# test2.net
KiCad netlist of a schematic drawn in EAGLE
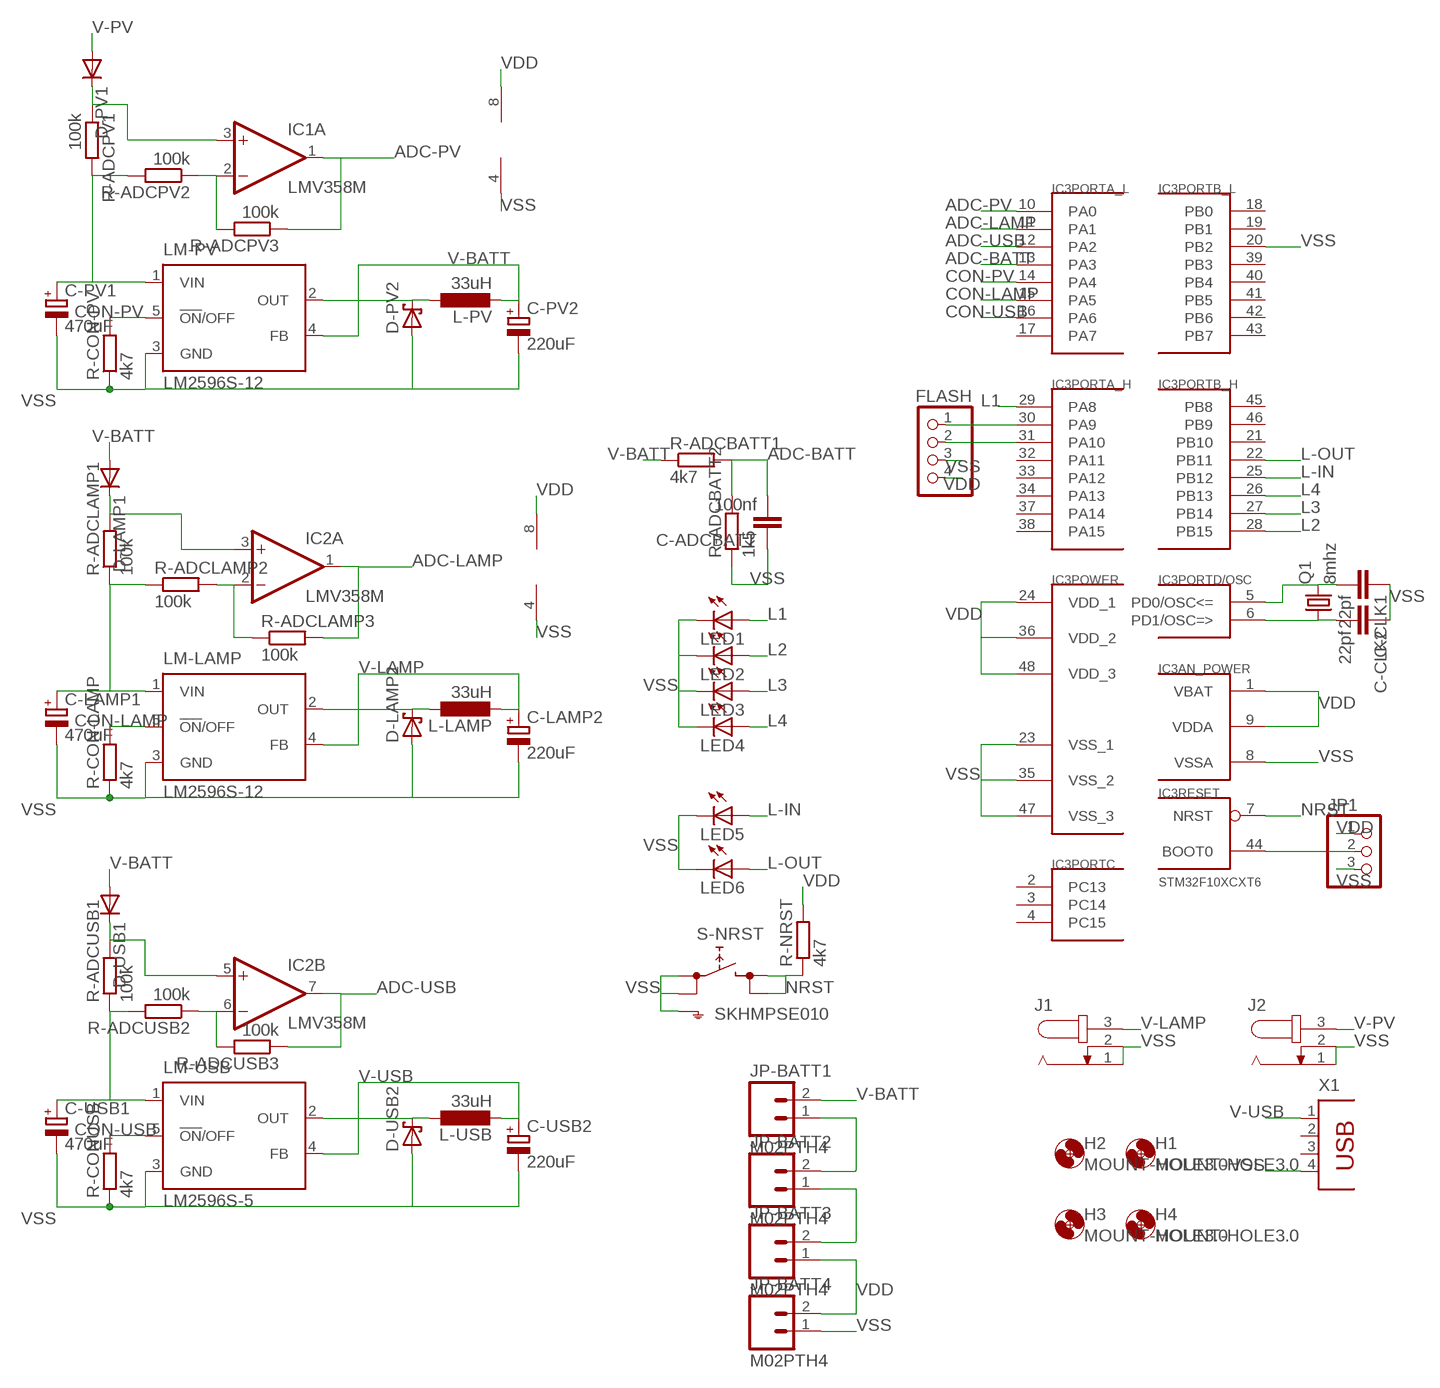
[diagram p0: schematic, sheet 1]

(export (version "E")
  (design (tool "Eeschema 10.0.6"))
  (components
    (comp (ref "C-ADCBATT")
      (value "100nf")
      (footprint "eagle-import:C0805")
      (libsource (lib "eagle-import") (part "C-EUC0805"))
    )
    (comp (ref "C-CLK1")
      (value "22pf")
      (footprint "eagle-import:C0805")
      (libsource (lib "eagle-import") (part "C-EUC0805"))
    )
    (comp (ref "C-CLK2")
      (value "22pf")
      (footprint "eagle-import:C0805")
      (libsource (lib "eagle-import") (part "C-EUC0805"))
    )
    (comp (ref "C-LAMP1")
      (value "470uF")
      (footprint "eagle-import:E2,5-5")
      (libsource (lib "eagle-import") (part "CPOL-EUE2.5-5"))
    )
    (comp (ref "C-LAMP2")
      (value "220uF")
      (footprint "eagle-import:E2,5-5")
      (libsource (lib "eagle-import") (part "CPOL-EUE2.5-5"))
    )
    (comp (ref "C-PV1")
      (value "470uF")
      (footprint "eagle-import:E2,5-5")
      (libsource (lib "eagle-import") (part "CPOL-EUE2.5-5"))
    )
    (comp (ref "C-PV2")
      (value "220uF")
      (footprint "eagle-import:E2,5-5")
      (libsource (lib "eagle-import") (part "CPOL-EUE2.5-5"))
    )
    (comp (ref "C-USB1")
      (value "470uF")
      (footprint "eagle-import:E2,5-5")
      (libsource (lib "eagle-import") (part "CPOL-EUE2.5-5"))
    )
    (comp (ref "C-USB2")
      (value "220uF")
      (footprint "eagle-import:E2,5-5")
      (libsource (lib "eagle-import") (part "CPOL-EUE2.5-5"))
    )
    (comp (ref "D-LAMP1")
      (value "DIODE-DO-214AC")
      (footprint "eagle-import:DO-214AC")
      (libsource (lib "eagle-import") (part "DIODE-DO-214AC"))
    )
    (comp (ref "D-LAMP2")
      (value "SCHOTTKY-DIODE")
      (footprint "eagle-import:DIODE_SMB")
      (libsource (lib "eagle-import") (part "SCHOTTKY-DIODE"))
    )
    (comp (ref "D-PV1")
      (value "DIODE-DO-214AC")
      (footprint "eagle-import:DO-214AC")
      (libsource (lib "eagle-import") (part "DIODE-DO-214AC"))
    )
    (comp (ref "D-PV2")
      (value "SCHOTTKY-DIODE")
      (footprint "eagle-import:DIODE_SMB")
      (libsource (lib "eagle-import") (part "SCHOTTKY-DIODE"))
    )
    (comp (ref "D-USB1")
      (value "DIODE-DO-214AC")
      (footprint "eagle-import:DO-214AC")
      (libsource (lib "eagle-import") (part "DIODE-DO-214AC"))
    )
    (comp (ref "D-USB2")
      (value "SCHOTTKY-DIODE")
      (footprint "eagle-import:DIODE_SMB")
      (libsource (lib "eagle-import") (part "SCHOTTKY-DIODE"))
    )
    (comp (ref "FLASH")
      (value "PINHD-1X4")
      (footprint "eagle-import:1X04")
      (libsource (lib "eagle-import") (part "PINHD-1X4"))
    )
    (comp (ref "H1")
      (value "MOUNT-HOLE3.0")
      (footprint "eagle-import:3,0")
      (libsource (lib "eagle-import") (part "MOUNT-HOLE3.0"))
    )
    (comp (ref "H2")
      (value "MOUNT-HOLE3.0")
      (footprint "eagle-import:3,0")
      (libsource (lib "eagle-import") (part "MOUNT-HOLE3.0"))
    )
    (comp (ref "H3")
      (value "MOUNT-HOLE3.0")
      (footprint "eagle-import:3,0")
      (libsource (lib "eagle-import") (part "MOUNT-HOLE3.0"))
    )
    (comp (ref "H4")
      (value "MOUNT-HOLE3.0")
      (footprint "eagle-import:3,0")
      (libsource (lib "eagle-import") (part "MOUNT-HOLE3.0"))
    )
    (comp (ref "IC1")
      (value "LMV358M")
      (footprint "eagle-import:SO08")
      (libsource (lib "eagle-import") (part "LMV358?M"))
    )
    (comp (ref "IC2")
      (value "LMV358M")
      (footprint "eagle-import:SO08")
      (libsource (lib "eagle-import") (part "LMV358?M"))
    )
    (comp (ref "IC3")
      (value "STM32F10XCXT6")
      (footprint "eagle-import:TQFP48")
      (libsource (lib "eagle-import") (part "STM32F10XCXT6"))
    )
    (comp (ref "J1")
      (value "JACK-PLUG0")
      (footprint "eagle-import:SPC4077")
      (libsource (lib "eagle-import") (part "JACK-PLUG0"))
    )
    (comp (ref "J2")
      (value "JACK-PLUG0")
      (footprint "eagle-import:SPC4077")
      (libsource (lib "eagle-import") (part "JACK-PLUG0"))
    )
    (comp (ref "JP-BATT1")
      (value "M02PTH4")
      (footprint "eagle-import:1X02_XTRA_BIG")
      (libsource (lib "eagle-import") (part "M02PTH4"))
    )
    (comp (ref "JP-BATT2")
      (value "M02PTH4")
      (footprint "eagle-import:1X02_XTRA_BIG")
      (libsource (lib "eagle-import") (part "M02PTH4"))
    )
    (comp (ref "JP-BATT3")
      (value "M02PTH4")
      (footprint "eagle-import:1X02_XTRA_BIG")
      (libsource (lib "eagle-import") (part "M02PTH4"))
    )
    (comp (ref "JP-BATT4")
      (value "M02PTH4")
      (footprint "eagle-import:1X02_XTRA_BIG")
      (libsource (lib "eagle-import") (part "M02PTH4"))
    )
    (comp (ref "JP1")
      (value "PINHD-1X3")
      (footprint "eagle-import:1X03")
      (libsource (lib "eagle-import") (part "PINHD-1X3"))
    )
    (comp (ref "L-LAMP")
      (value "33uH")
      (footprint "eagle-import:POWER-CHOKE_WE-TPC")
      (libsource (lib "eagle-import") (part "L-EUWE-TPC"))
    )
    (comp (ref "L-PV")
      (value "33uH")
      (footprint "eagle-import:POWER-CHOKE_WE-TPC")
      (libsource (lib "eagle-import") (part "L-EUWE-TPC"))
    )
    (comp (ref "L-USB")
      (value "33uH")
      (footprint "eagle-import:POWER-CHOKE_WE-TPC")
      (libsource (lib "eagle-import") (part "L-EUWE-TPC"))
    )
    (comp (ref "LED1")
      (value "LEDCHIP-LED0805")
      (footprint "eagle-import:CHIP-LED0805")
      (libsource (lib "eagle-import") (part "LEDCHIP-LED0805"))
    )
    (comp (ref "LED2")
      (value "LEDCHIP-LED0805")
      (footprint "eagle-import:CHIP-LED0805")
      (libsource (lib "eagle-import") (part "LEDCHIP-LED0805"))
    )
    (comp (ref "LED3")
      (value "LEDCHIP-LED0805")
      (footprint "eagle-import:CHIP-LED0805")
      (libsource (lib "eagle-import") (part "LEDCHIP-LED0805"))
    )
    (comp (ref "LED4")
      (value "LEDCHIP-LED0805")
      (footprint "eagle-import:CHIP-LED0805")
      (libsource (lib "eagle-import") (part "LEDCHIP-LED0805"))
    )
    (comp (ref "LED5")
      (value "LEDCHIP-LED0805")
      (footprint "eagle-import:CHIP-LED0805")
      (libsource (lib "eagle-import") (part "LEDCHIP-LED0805"))
    )
    (comp (ref "LED6")
      (value "LEDCHIP-LED0805")
      (footprint "eagle-import:CHIP-LED0805")
      (libsource (lib "eagle-import") (part "LEDCHIP-LED0805"))
    )
    (comp (ref "LM-LAMP")
      (value "LM2596S-12")
      (footprint "eagle-import:TO263-5")
      (fields (field (name "MF") "NATIONAL SEMICONDUCTOR") (field (name "MPN") "LM2596S-ADJ/NOPB"))
      (libsource (lib "eagle-import") (part "LM2596S"))
    )
    (comp (ref "LM-PV")
      (value "LM2596S-12")
      (footprint "eagle-import:TO263-5")
      (fields (field (name "MF") "NATIONAL SEMICONDUCTOR") (field (name "MPN") "LM2596S-ADJ/NOPB"))
      (libsource (lib "eagle-import") (part "LM2596S"))
    )
    (comp (ref "LM-USB")
      (value "LM2596S-5")
      (footprint "eagle-import:TO263-5")
      (fields (field (name "MF") "NATIONAL SEMICONDUCTOR") (field (name "MPN") "LM2596S-ADJ/NOPB"))
      (libsource (lib "eagle-import") (part "LM2596S"))
    )
    (comp (ref "Q1")
      (value "8mhz")
      (footprint "eagle-import:HC49_S")
      (libsource (lib "eagle-import") (part "CRYSTALHC49S"))
    )
    (comp (ref "R-ADCBATT1")
      (value "4k7")
      (footprint "eagle-import:R0805")
      (libsource (lib "eagle-import") (part "R-EU_R0805"))
    )
    (comp (ref "R-ADCBATT2")
      (value "1k5")
      (footprint "eagle-import:R0805")
      (libsource (lib "eagle-import") (part "R-EU_R0805"))
    )
    (comp (ref "R-ADCLAMP1")
      (value "100k")
      (footprint "eagle-import:R0805")
      (libsource (lib "eagle-import") (part "R-EU_R0805"))
    )
    (comp (ref "R-ADCLAMP2")
      (value "100k")
      (footprint "eagle-import:R0805")
      (libsource (lib "eagle-import") (part "R-EU_R0805"))
    )
    (comp (ref "R-ADCLAMP3")
      (value "100k")
      (footprint "eagle-import:R0805")
      (libsource (lib "eagle-import") (part "R-EU_R0805"))
    )
    (comp (ref "R-ADCPV1")
      (value "100k")
      (footprint "eagle-import:R0805")
      (libsource (lib "eagle-import") (part "R-EU_R0805"))
    )
    (comp (ref "R-ADCPV2")
      (value "100k")
      (footprint "eagle-import:R0805")
      (libsource (lib "eagle-import") (part "R-EU_R0805"))
    )
    (comp (ref "R-ADCPV3")
      (value "100k")
      (footprint "eagle-import:R0805")
      (libsource (lib "eagle-import") (part "R-EU_R0805"))
    )
    (comp (ref "R-ADCUSB1")
      (value "100k")
      (footprint "eagle-import:R0805")
      (libsource (lib "eagle-import") (part "R-EU_R0805"))
    )
    (comp (ref "R-ADCUSB2")
      (value "100k")
      (footprint "eagle-import:R0805")
      (libsource (lib "eagle-import") (part "R-EU_R0805"))
    )
    (comp (ref "R-ADCUSB3")
      (value "100k")
      (footprint "eagle-import:R0805")
      (libsource (lib "eagle-import") (part "R-EU_R0805"))
    )
    (comp (ref "R-CON-LAMP")
      (value "4k7")
      (footprint "eagle-import:R0805")
      (libsource (lib "eagle-import") (part "R-EU_R0805"))
    )
    (comp (ref "R-CON-PV")
      (value "4k7")
      (footprint "eagle-import:R0805")
      (libsource (lib "eagle-import") (part "R-EU_R0805"))
    )
    (comp (ref "R-CONUSB")
      (value "4k7")
      (footprint "eagle-import:R0805")
      (libsource (lib "eagle-import") (part "R-EU_R0805"))
    )
    (comp (ref "R-NRST")
      (value "4k7")
      (footprint "eagle-import:R0805")
      (libsource (lib "eagle-import") (part "R-EU_R0805"))
    )
    (comp (ref "S-NRST")
      (value "SKHMPSE010")
      (footprint "eagle-import:SKHMPXE010")
      (libsource (lib "eagle-import") (part "SKHMPE010S"))
    )
    (comp (ref "X1")
      (value "PN87520")
      (footprint "eagle-import:PN87520")
      (libsource (lib "eagle-import") (part "PN87520"))
    )
  )
  (nets
    (net (code "1") (name "/ADC-BATT") (class "Default")
      (node (ref "C-ADCBATT") (pin "2") (pinfunction "2_2") (pintype "passive"))
      (node (ref "IC3") (pin "13") (pinfunction "PA3_13") (pintype "bidirectional"))
      (node (ref "R-ADCBATT1") (pin "2") (pinfunction "2_2") (pintype "passive"))
      (node (ref "R-ADCBATT2") (pin "2") (pinfunction "2_2") (pintype "passive"))
    )
    (net (code "2") (name "/ADC-LAMP") (class "Default")
      (node (ref "IC2") (pin "1") (pinfunction "OUT_1") (pintype "output"))
      (node (ref "IC3") (pin "11") (pinfunction "PA1_11") (pintype "bidirectional"))
      (node (ref "R-ADCLAMP3") (pin "2") (pinfunction "2_2") (pintype "passive"))
    )
    (net (code "3") (name "/ADC-PV") (class "Default")
      (node (ref "IC1") (pin "1") (pinfunction "OUT_1") (pintype "output"))
      (node (ref "IC3") (pin "10") (pinfunction "PA0_10") (pintype "bidirectional"))
      (node (ref "R-ADCPV3") (pin "1") (pinfunction "1_1") (pintype "passive"))
    )
    (net (code "4") (name "/ADC-USB") (class "Default")
      (node (ref "IC2") (pin "7") (pinfunction "OUT_7") (pintype "output"))
      (node (ref "IC3") (pin "12") (pinfunction "PA2_12") (pintype "bidirectional"))
      (node (ref "R-ADCUSB3") (pin "1") (pinfunction "1_1") (pintype "passive"))
    )
    (net (code "5") (name "/CON-LAMP") (class "Default")
      (node (ref "IC3") (pin "15") (pinfunction "PA5_15") (pintype "bidirectional"))
      (node (ref "LM-LAMP") (pin "5") (pinfunction "~{ON}/OFF_5") (pintype "input"))
      (node (ref "R-CON-LAMP") (pin "2") (pinfunction "2_2") (pintype "passive"))
    )
    (net (code "6") (name "/CON-PV") (class "Default")
      (node (ref "IC3") (pin "14") (pinfunction "PA4_14") (pintype "bidirectional"))
      (node (ref "LM-PV") (pin "5") (pinfunction "~{ON}/OFF_5") (pintype "input"))
      (node (ref "R-CON-PV") (pin "2") (pinfunction "2_2") (pintype "passive"))
    )
    (net (code "7") (name "/CON-USB") (class "Default")
      (node (ref "IC3") (pin "16") (pinfunction "PA6_16") (pintype "bidirectional"))
      (node (ref "LM-USB") (pin "5") (pinfunction "~{ON}/OFF_5") (pintype "input"))
      (node (ref "R-CONUSB") (pin "2") (pinfunction "2_2") (pintype "passive"))
    )
    (net (code "8") (name "/L-IN") (class "Default")
      (node (ref "IC3") (pin "25") (pinfunction "PB12_25") (pintype "bidirectional"))
      (node (ref "LED5") (pin "A") (pinfunction "A_A") (pintype "passive"))
    )
    (net (code "9") (name "/L-OUT") (class "Default")
      (node (ref "IC3") (pin "22") (pinfunction "PB11_22") (pintype "bidirectional"))
      (node (ref "LED6") (pin "A") (pinfunction "A_A") (pintype "passive"))
    )
    (net (code "10") (name "/L1") (class "Default")
      (node (ref "IC3") (pin "29") (pinfunction "PA8_29") (pintype "bidirectional"))
      (node (ref "LED1") (pin "A") (pinfunction "A_A") (pintype "passive"))
    )
    (net (code "11") (name "/L2") (class "Default")
      (node (ref "IC3") (pin "28") (pinfunction "PB15_28") (pintype "bidirectional"))
      (node (ref "LED2") (pin "A") (pinfunction "A_A") (pintype "passive"))
    )
    (net (code "12") (name "/L3") (class "Default")
      (node (ref "IC3") (pin "27") (pinfunction "PB14_27") (pintype "bidirectional"))
      (node (ref "LED3") (pin "A") (pinfunction "A_A") (pintype "passive"))
    )
    (net (code "13") (name "/L4") (class "Default")
      (node (ref "IC3") (pin "26") (pinfunction "PB13_26") (pintype "bidirectional"))
      (node (ref "LED4") (pin "A") (pinfunction "A_A") (pintype "passive"))
    )
    (net (code "14") (name "/NRST") (class "Default")
      (node (ref "IC3") (pin "7") (pinfunction "NRST_7") (pintype "input"))
      (node (ref "R-NRST") (pin "1") (pinfunction "1_1") (pintype "passive"))
      (node (ref "S-NRST") (pin "3") (pinfunction "2.1_3") (pintype "passive"))
      (node (ref "S-NRST") (pin "4") (pinfunction "2.2_4") (pintype "passive"))
    )
    (net (code "15") (name "/V-BATT") (class "Default")
      (node (ref "C-PV2") (pin "+") (pinfunction "+_+") (pintype "passive"))
      (node (ref "D-LAMP1") (pin "A") (pinfunction "A_A") (pintype "passive"))
      (node (ref "D-USB1") (pin "A") (pinfunction "A_A") (pintype "passive"))
      (node (ref "JP-BATT1") (pin "2") (pinfunction "2_2") (pintype "passive"))
      (node (ref "L-PV") (pin "2") (pinfunction "2_2") (pintype "passive"))
      (node (ref "LM-PV") (pin "4") (pinfunction "FB_4") (pintype "input"))
      (node (ref "R-ADCBATT1") (pin "1") (pinfunction "1_1") (pintype "passive"))
    )
    (net (code "16") (name "/V-LAMP") (class "Default")
      (node (ref "C-LAMP2") (pin "+") (pinfunction "+_+") (pintype "passive"))
      (node (ref "J1") (pin "3") (pinfunction "3_3") (pintype "passive"))
      (node (ref "L-LAMP") (pin "2") (pinfunction "2_2") (pintype "passive"))
      (node (ref "LM-LAMP") (pin "4") (pinfunction "FB_4") (pintype "input"))
    )
    (net (code "17") (name "/V-PV") (class "Default")
      (node (ref "D-PV1") (pin "A") (pinfunction "A_A") (pintype "passive"))
      (node (ref "J2") (pin "3") (pinfunction "3_3") (pintype "passive"))
    )
    (net (code "18") (name "/V-USB") (class "Default")
      (node (ref "C-USB2") (pin "+") (pinfunction "+_+") (pintype "passive"))
      (node (ref "L-USB") (pin "2") (pinfunction "2_2") (pintype "passive"))
      (node (ref "LM-USB") (pin "4") (pinfunction "FB_4") (pintype "input"))
      (node (ref "X1") (pin "1") (pinfunction "1_1") (pintype "passive"))
    )
    (net (code "19") (name "/VDD") (class "Default")
      (node (ref "FLASH") (pin "4") (pinfunction "4_4") (pintype "passive"))
      (node (ref "IC1") (pin "8") (pinfunction "V+_8") (pintype "power_in"))
      (node (ref "IC2") (pin "8") (pinfunction "V+_8") (pintype "power_in"))
      (node (ref "IC3") (pin "1") (pinfunction "VBAT_1") (pintype "power_in"))
      (node (ref "IC3") (pin "24") (pinfunction "VDD_1_24") (pintype "power_in"))
      (node (ref "IC3") (pin "36") (pinfunction "VDD_2_36") (pintype "power_in"))
      (node (ref "IC3") (pin "48") (pinfunction "VDD_3_48") (pintype "power_in"))
      (node (ref "IC3") (pin "9") (pinfunction "VDDA_9") (pintype "power_in"))
      (node (ref "JP-BATT3") (pin "1") (pinfunction "1_1") (pintype "passive"))
      (node (ref "JP-BATT4") (pin "2") (pinfunction "2_2") (pintype "passive"))
      (node (ref "JP1") (pin "1") (pinfunction "1_1") (pintype "passive"))
      (node (ref "R-NRST") (pin "2") (pinfunction "2_2") (pintype "passive"))
    )
    (net (code "20") (name "/VSS") (class "Default")
      (node (ref "C-ADCBATT") (pin "1") (pinfunction "1_1") (pintype "passive"))
      (node (ref "C-CLK1") (pin "1") (pinfunction "1_1") (pintype "passive"))
      (node (ref "C-CLK2") (pin "1") (pinfunction "1_1") (pintype "passive"))
      (node (ref "C-LAMP1") (pin "-") (pinfunction "-_-") (pintype "passive"))
      (node (ref "C-LAMP2") (pin "-") (pinfunction "-_-") (pintype "passive"))
      (node (ref "C-PV1") (pin "-") (pinfunction "-_-") (pintype "passive"))
      (node (ref "C-PV2") (pin "-") (pinfunction "-_-") (pintype "passive"))
      (node (ref "C-USB1") (pin "-") (pinfunction "-_-") (pintype "passive"))
      (node (ref "C-USB2") (pin "-") (pinfunction "-_-") (pintype "passive"))
      (node (ref "D-LAMP2") (pin "A") (pinfunction "C_A") (pintype "passive"))
      (node (ref "D-PV2") (pin "A") (pinfunction "C_A") (pintype "passive"))
      (node (ref "D-USB2") (pin "A") (pinfunction "C_A") (pintype "passive"))
      (node (ref "FLASH") (pin "3") (pinfunction "3_3") (pintype "passive"))
      (node (ref "IC1") (pin "4") (pinfunction "V-_4") (pintype "power_in"))
      (node (ref "IC2") (pin "4") (pinfunction "V-_4") (pintype "power_in"))
      (node (ref "IC3") (pin "20") (pinfunction "PB2_20") (pintype "bidirectional"))
      (node (ref "IC3") (pin "23") (pinfunction "VSS_1_23") (pintype "power_in"))
      (node (ref "IC3") (pin "35") (pinfunction "VSS_2_35") (pintype "power_in"))
      (node (ref "IC3") (pin "47") (pinfunction "VSS_3_47") (pintype "power_in"))
      (node (ref "IC3") (pin "8") (pinfunction "VSSA_8") (pintype "power_in"))
      (node (ref "J1") (pin "1") (pinfunction "1_1") (pintype "passive"))
      (node (ref "J1") (pin "2") (pinfunction "2_2") (pintype "passive"))
      (node (ref "J2") (pin "1") (pinfunction "1_1") (pintype "passive"))
      (node (ref "J2") (pin "2") (pinfunction "2_2") (pintype "passive"))
      (node (ref "JP-BATT4") (pin "1") (pinfunction "1_1") (pintype "passive"))
      (node (ref "JP1") (pin "3") (pinfunction "3_3") (pintype "passive"))
      (node (ref "LED1") (pin "C") (pinfunction "C_C") (pintype "passive"))
      (node (ref "LED2") (pin "C") (pinfunction "C_C") (pintype "passive"))
      (node (ref "LED3") (pin "C") (pinfunction "C_C") (pintype "passive"))
      (node (ref "LED4") (pin "C") (pinfunction "C_C") (pintype "passive"))
      (node (ref "LED5") (pin "C") (pinfunction "C_C") (pintype "passive"))
      (node (ref "LED6") (pin "C") (pinfunction "C_C") (pintype "passive"))
      (node (ref "LM-LAMP") (pin "3") (pinfunction "GND_3") (pintype "power_in"))
      (node (ref "LM-PV") (pin "3") (pinfunction "GND_3") (pintype "power_in"))
      (node (ref "LM-USB") (pin "3") (pinfunction "GND_3") (pintype "power_in"))
      (node (ref "R-ADCBATT2") (pin "1") (pinfunction "1_1") (pintype "passive"))
      (node (ref "R-CON-LAMP") (pin "1") (pinfunction "1_1") (pintype "passive"))
      (node (ref "R-CON-PV") (pin "1") (pinfunction "1_1") (pintype "passive"))
      (node (ref "R-CONUSB") (pin "1") (pinfunction "1_1") (pintype "passive"))
      (node (ref "S-NRST") (pin "1") (pinfunction "1.1_1") (pintype "passive"))
      (node (ref "S-NRST") (pin "2") (pinfunction "1.2_2") (pintype "passive"))
      (node (ref "S-NRST") (pin "5") (pinfunction "SH_5") (pintype "passive"))
      (node (ref "X1") (pin "4") (pinfunction "4_4") (pintype "passive"))
    )
    (net (code "21") (name "Net-(D-LAMP2-A)") (class "Default")
      (node (ref "D-LAMP2") (pin "C") (pinfunction "A_C") (pintype "passive"))
      (node (ref "L-LAMP") (pin "1") (pinfunction "1_1") (pintype "passive"))
      (node (ref "LM-LAMP") (pin "2") (pinfunction "OUT_2") (pintype "output"))
    )
    (net (code "22") (name "Net-(D-PV2-A)") (class "Default")
      (node (ref "D-PV2") (pin "C") (pinfunction "A_C") (pintype "passive"))
      (node (ref "L-PV") (pin "1") (pinfunction "1_1") (pintype "passive"))
      (node (ref "LM-PV") (pin "2") (pinfunction "OUT_2") (pintype "output"))
    )
    (net (code "23") (name "Net-(D-USB2-A)") (class "Default")
      (node (ref "D-USB2") (pin "C") (pinfunction "A_C") (pintype "passive"))
      (node (ref "L-USB") (pin "1") (pinfunction "1_1") (pintype "passive"))
      (node (ref "LM-USB") (pin "2") (pinfunction "OUT_2") (pintype "output"))
    )
    (net (code "24") (name "Net-(IC1A-+IN)") (class "Default")
      (node (ref "D-PV1") (pin "C") (pinfunction "C_C") (pintype "passive"))
      (node (ref "IC1") (pin "3") (pinfunction "+IN_3") (pintype "input"))
      (node (ref "R-ADCPV1") (pin "1") (pinfunction "1_1") (pintype "passive"))
    )
    (net (code "25") (name "Net-(IC1A--IN)") (class "Default")
      (node (ref "IC1") (pin "2") (pinfunction "-IN_2") (pintype "input"))
      (node (ref "R-ADCPV2") (pin "1") (pinfunction "1_1") (pintype "passive"))
      (node (ref "R-ADCPV3") (pin "2") (pinfunction "2_2") (pintype "passive"))
    )
    (net (code "26") (name "Net-(IC2A-+IN)") (class "Default")
      (node (ref "D-LAMP1") (pin "C") (pinfunction "C_C") (pintype "passive"))
      (node (ref "IC2") (pin "3") (pinfunction "+IN_3") (pintype "input"))
      (node (ref "R-ADCLAMP1") (pin "2") (pinfunction "2_2") (pintype "passive"))
    )
    (net (code "27") (name "Net-(IC2A--IN)") (class "Default")
      (node (ref "IC2") (pin "2") (pinfunction "-IN_2") (pintype "input"))
      (node (ref "R-ADCLAMP2") (pin "2") (pinfunction "2_2") (pintype "passive"))
      (node (ref "R-ADCLAMP3") (pin "1") (pinfunction "1_1") (pintype "passive"))
    )
    (net (code "28") (name "Net-(IC2B-+IN)") (class "Default")
      (node (ref "D-USB1") (pin "C") (pinfunction "C_C") (pintype "passive"))
      (node (ref "IC2") (pin "5") (pinfunction "+IN_5") (pintype "input"))
      (node (ref "R-ADCUSB1") (pin "2") (pinfunction "2_2") (pintype "passive"))
    )
    (net (code "29") (name "Net-(IC2B--IN)") (class "Default")
      (node (ref "IC2") (pin "6") (pinfunction "-IN_6") (pintype "input"))
      (node (ref "R-ADCUSB2") (pin "1") (pinfunction "1_1") (pintype "passive"))
      (node (ref "R-ADCUSB3") (pin "2") (pinfunction "2_2") (pintype "passive"))
    )
    (net (code "30") (name "Net-(IC3B-PA9)") (class "Default")
      (node (ref "FLASH") (pin "1") (pinfunction "1_1") (pintype "passive"))
      (node (ref "IC3") (pin "30") (pinfunction "PA9_30") (pintype "bidirectional"))
    )
    (net (code "31") (name "Net-(IC3B-PA10)") (class "Default")
      (node (ref "FLASH") (pin "2") (pinfunction "2_2") (pintype "passive"))
      (node (ref "IC3") (pin "31") (pinfunction "PA10_31") (pintype "bidirectional"))
    )
    (net (code "32") (name "Net-(IC3G-PD0{slash}OSC<=)") (class "Default")
      (node (ref "C-CLK1") (pin "2") (pinfunction "2_2") (pintype "passive"))
      (node (ref "IC3") (pin "5") (pinfunction "PD0/OSC<=_5") (pintype "bidirectional"))
      (node (ref "Q1") (pin "2") (pinfunction "2_2") (pintype "passive"))
    )
    (net (code "33") (name "Net-(IC3G-PD1{slash}OSC=>)") (class "Default")
      (node (ref "C-CLK2") (pin "2") (pinfunction "2_2") (pintype "passive"))
      (node (ref "IC3") (pin "6") (pinfunction "PD1/OSC=>_6") (pintype "bidirectional"))
      (node (ref "Q1") (pin "1") (pinfunction "1_1") (pintype "passive"))
    )
    (net (code "34") (name "Net-(IC3I-BOOT0)") (class "Default")
      (node (ref "IC3") (pin "44") (pinfunction "BOOT0_44") (pintype "input"))
      (node (ref "JP1") (pin "2") (pinfunction "2_2") (pintype "passive"))
    )
    (net (code "35") (name "Net-(JP-BATT1-Pad1)") (class "Default")
      (node (ref "JP-BATT1") (pin "1") (pinfunction "1_1") (pintype "passive"))
      (node (ref "JP-BATT2") (pin "2") (pinfunction "2_2") (pintype "passive"))
    )
    (net (code "36") (name "Net-(JP-BATT2-Pad1)") (class "Default")
      (node (ref "JP-BATT2") (pin "1") (pinfunction "1_1") (pintype "passive"))
      (node (ref "JP-BATT3") (pin "2") (pinfunction "2_2") (pintype "passive"))
    )
    (net (code "37") (name "Net-(LM-LAMP-VIN)") (class "Default")
      (node (ref "C-LAMP1") (pin "+") (pinfunction "+_+") (pintype "passive"))
      (node (ref "LM-LAMP") (pin "1") (pinfunction "VIN_1") (pintype "input"))
      (node (ref "R-ADCLAMP1") (pin "1") (pinfunction "1_1") (pintype "passive"))
      (node (ref "R-ADCLAMP2") (pin "1") (pinfunction "1_1") (pintype "passive"))
    )
    (net (code "38") (name "Net-(LM-PV-VIN)") (class "Default")
      (node (ref "C-PV1") (pin "+") (pinfunction "+_+") (pintype "passive"))
      (node (ref "LM-PV") (pin "1") (pinfunction "VIN_1") (pintype "input"))
      (node (ref "R-ADCPV1") (pin "2") (pinfunction "2_2") (pintype "passive"))
      (node (ref "R-ADCPV2") (pin "2") (pinfunction "2_2") (pintype "passive"))
    )
    (net (code "39") (name "Net-(LM-USB-VIN)") (class "Default")
      (node (ref "C-USB1") (pin "+") (pinfunction "+_+") (pintype "passive"))
      (node (ref "LM-USB") (pin "1") (pinfunction "VIN_1") (pintype "input"))
      (node (ref "R-ADCUSB1") (pin "1") (pinfunction "1_1") (pintype "passive"))
      (node (ref "R-ADCUSB2") (pin "2") (pinfunction "2_2") (pintype "passive"))
    )
    (net (code "40") (name "unconnected-(IC3B-PA11-Pad32)") (class "Default")
      (node (ref "IC3") (pin "32") (pinfunction "PA11_32") (pintype "bidirectional"))
    )
    (net (code "41") (name "unconnected-(IC3B-PA12-Pad33)") (class "Default")
      (node (ref "IC3") (pin "33") (pinfunction "PA12_33") (pintype "bidirectional"))
    )
    (net (code "42") (name "unconnected-(IC3B-PA13-Pad34)") (class "Default")
      (node (ref "IC3") (pin "34") (pinfunction "PA13_34") (pintype "bidirectional"))
    )
    (net (code "43") (name "unconnected-(IC3B-PA14-Pad37)") (class "Default")
      (node (ref "IC3") (pin "37") (pinfunction "PA14_37") (pintype "bidirectional"))
    )
    (net (code "44") (name "unconnected-(IC3B-PA15-Pad38)") (class "Default")
      (node (ref "IC3") (pin "38") (pinfunction "PA15_38") (pintype "bidirectional"))
    )
    (net (code "45") (name "unconnected-(IC3C-PA7-Pad17)") (class "Default")
      (node (ref "IC3") (pin "17") (pinfunction "PA7_17") (pintype "bidirectional"))
    )
    (net (code "46") (name "unconnected-(IC3D-PB8-Pad45)") (class "Default")
      (node (ref "IC3") (pin "45") (pinfunction "PB8_45") (pintype "bidirectional"))
    )
    (net (code "47") (name "unconnected-(IC3D-PB9-Pad46)") (class "Default")
      (node (ref "IC3") (pin "46") (pinfunction "PB9_46") (pintype "bidirectional"))
    )
    (net (code "48") (name "unconnected-(IC3D-PB10-Pad21)") (class "Default")
      (node (ref "IC3") (pin "21") (pinfunction "PB10_21") (pintype "bidirectional"))
    )
    (net (code "49") (name "unconnected-(IC3E-PB0-Pad18)") (class "Default")
      (node (ref "IC3") (pin "18") (pinfunction "PB0_18") (pintype "bidirectional"))
    )
    (net (code "50") (name "unconnected-(IC3E-PB1-Pad19)") (class "Default")
      (node (ref "IC3") (pin "19") (pinfunction "PB1_19") (pintype "bidirectional"))
    )
    (net (code "51") (name "unconnected-(IC3E-PB3-Pad39)") (class "Default")
      (node (ref "IC3") (pin "39") (pinfunction "PB3_39") (pintype "bidirectional"))
    )
    (net (code "52") (name "unconnected-(IC3E-PB4-Pad40)") (class "Default")
      (node (ref "IC3") (pin "40") (pinfunction "PB4_40") (pintype "bidirectional"))
    )
    (net (code "53") (name "unconnected-(IC3E-PB5-Pad41)") (class "Default")
      (node (ref "IC3") (pin "41") (pinfunction "PB5_41") (pintype "bidirectional"))
    )
    (net (code "54") (name "unconnected-(IC3E-PB6-Pad42)") (class "Default")
      (node (ref "IC3") (pin "42") (pinfunction "PB6_42") (pintype "bidirectional"))
    )
    (net (code "55") (name "unconnected-(IC3E-PB7-Pad43)") (class "Default")
      (node (ref "IC3") (pin "43") (pinfunction "PB7_43") (pintype "bidirectional"))
    )
    (net (code "56") (name "unconnected-(IC3F-PC13-Pad2)") (class "Default")
      (node (ref "IC3") (pin "2") (pinfunction "PC13_2") (pintype "bidirectional"))
    )
    (net (code "57") (name "unconnected-(IC3F-PC14-Pad3)") (class "Default")
      (node (ref "IC3") (pin "3") (pinfunction "PC14_3") (pintype "bidirectional"))
    )
    (net (code "58") (name "unconnected-(IC3F-PC15-Pad4)") (class "Default")
      (node (ref "IC3") (pin "4") (pinfunction "PC15_4") (pintype "bidirectional"))
    )
    (net (code "59") (name "unconnected-(X1-Pad2)") (class "Default")
      (node (ref "X1") (pin "2") (pinfunction "2_2") (pintype "passive"))
    )
    (net (code "60") (name "unconnected-(X1-Pad3)") (class "Default")
      (node (ref "X1") (pin "3") (pinfunction "3_3") (pintype "passive"))
    )
  )
)
